# VM_Motor.net
KiCad netlist of a schematic drawn in EAGLE
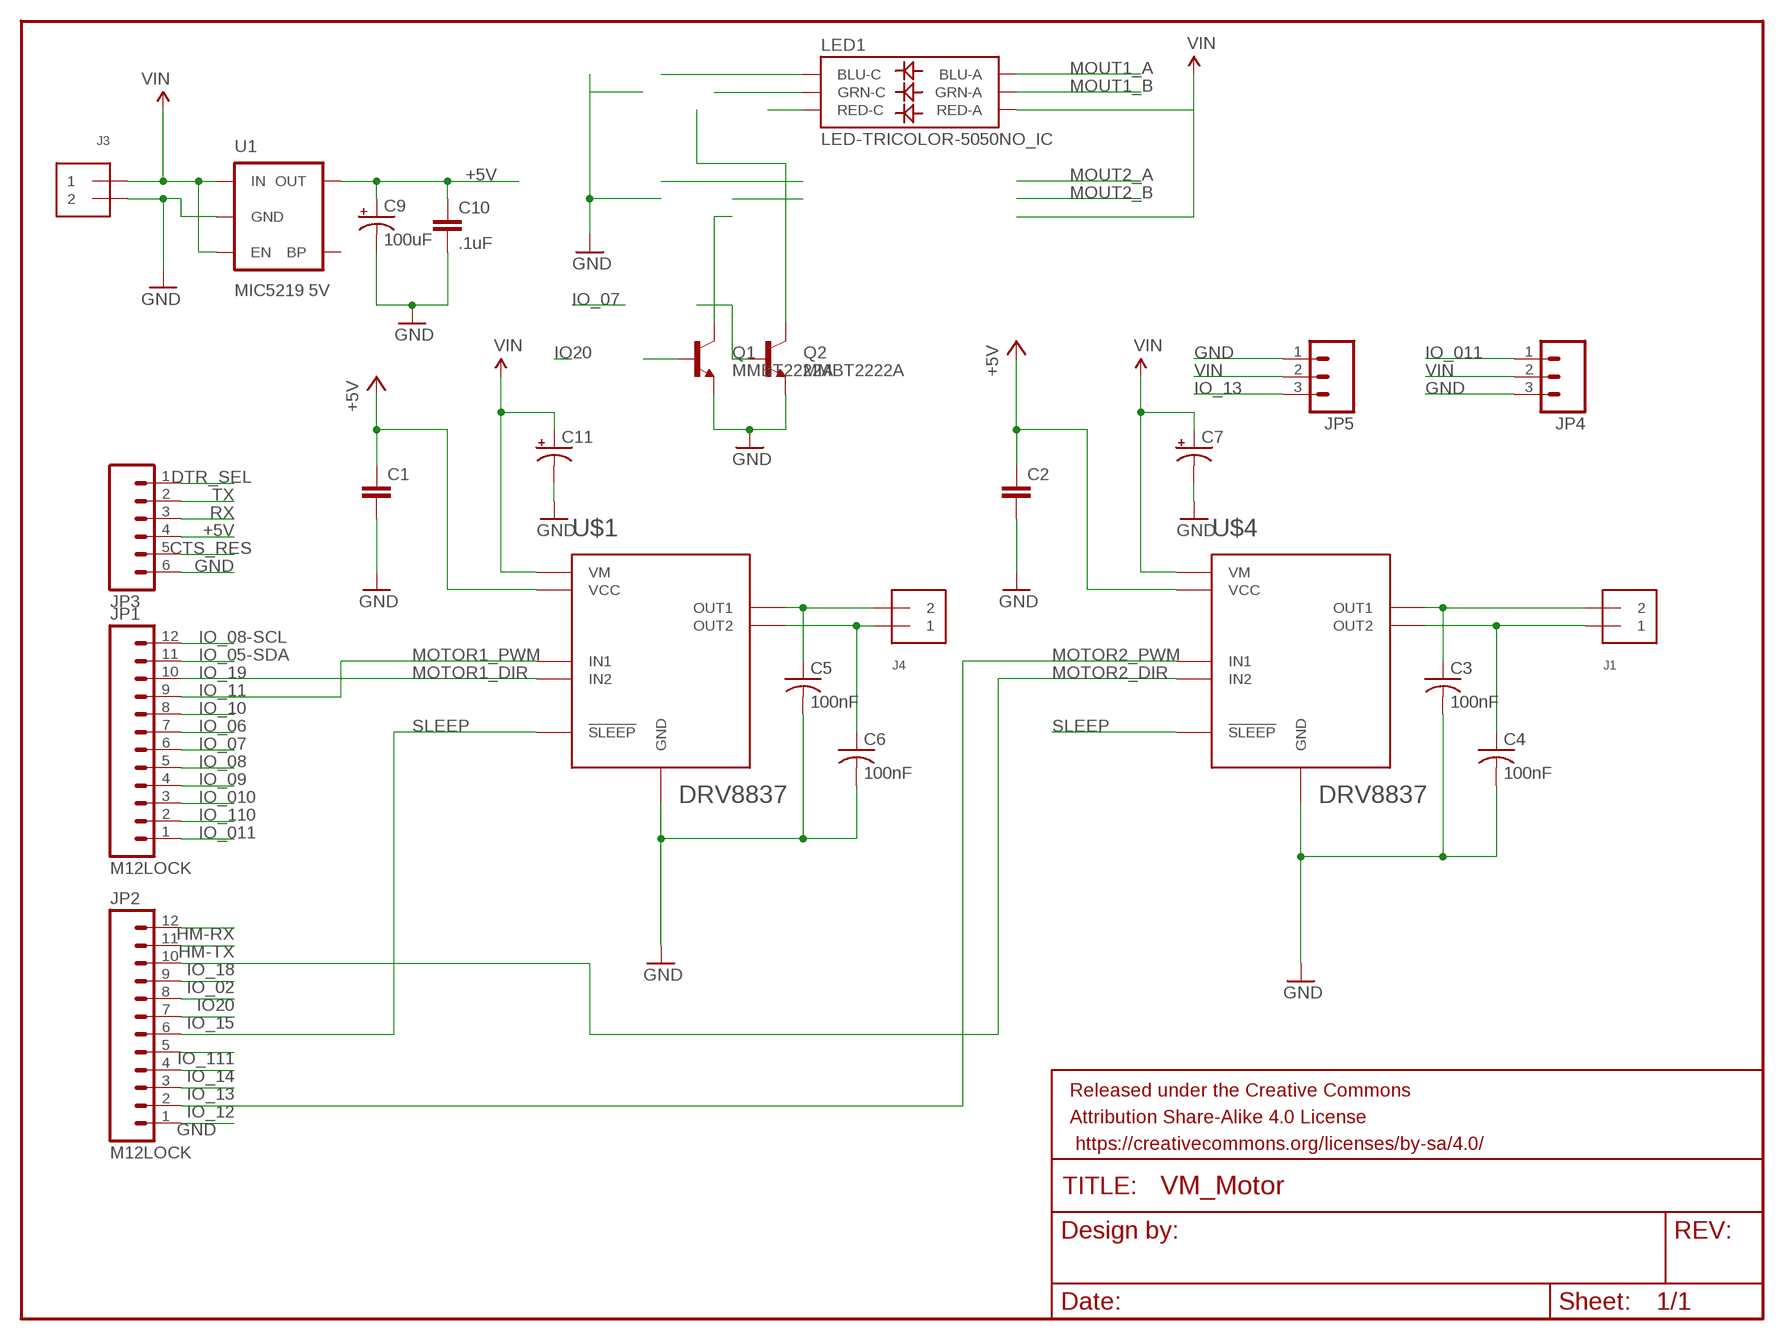
[diagram p0: schematic, sheet 1]

(export (version "E")
  (design (tool "Eeschema 10.0.6"))
  (components
    (comp (ref "C1")
      (value "CAP0402-CAP")
      (footprint "eagle-import:0402-CAP")
      (libsource (lib "eagle-import") (part "CAP0402-CAP"))
    )
    (comp (ref "C2")
      (value "CAP0402-CAP")
      (footprint "eagle-import:0402-CAP")
      (libsource (lib "eagle-import") (part "CAP0402-CAP"))
    )
    (comp (ref "C3")
      (value "100nF")
      (footprint "eagle-import:C0402")
      (libsource (lib "eagle-import") (part "C-USC0402"))
    )
    (comp (ref "C4")
      (value "100nF")
      (footprint "eagle-import:C0402")
      (libsource (lib "eagle-import") (part "C-USC0402"))
    )
    (comp (ref "C5")
      (value "100nF")
      (footprint "eagle-import:C0402")
      (libsource (lib "eagle-import") (part "C-USC0402"))
    )
    (comp (ref "C6")
      (value "100nF")
      (footprint "eagle-import:C0402")
      (libsource (lib "eagle-import") (part "C-USC0402"))
    )
    (comp (ref "C7")
      (value "CPOL-US140CLH-0810")
      (footprint "eagle-import:140CLH-0810")
      (libsource (lib "eagle-import") (part "CPOL-US140CLH-0810"))
    )
    (comp (ref "C9")
      (value "100uF")
      (footprint "eagle-import:EIA3528-KIT")
      (libsource (lib "eagle-import") (part "CAP_POL3528-KIT"))
    )
    (comp (ref "C10")
      (value ".1uF")
      (footprint "eagle-import:0402-CAP")
      (libsource (lib "eagle-import") (part "CAP0402-CAP"))
    )
    (comp (ref "C11")
      (value "CPOL-US140CLH-0810")
      (footprint "eagle-import:140CLH-0810")
      (libsource (lib "eagle-import") (part "CPOL-US140CLH-0810"))
    )
    (comp (ref "FRAME1")
      (value "FRAME-LETTER")
      (footprint "eagle-import:CREATIVE_COMMONS")
      (libsource (lib "eagle-import") (part "FRAME-LETTER"))
    )
    (comp (ref "J1")
      (value "TERMBLOCK_1X2")
      (footprint "eagle-import:TERMBLOCK_1X2-3.5MM")
      (libsource (lib "eagle-import") (part "TERMBLOCK_1X2"))
    )
    (comp (ref "J3")
      (value "TERMBLOCK_1X2")
      (footprint "eagle-import:TERMBLOCK_1X2-3.5MM")
      (libsource (lib "eagle-import") (part "TERMBLOCK_1X2"))
    )
    (comp (ref "J4")
      (value "TERMBLOCK_1X2")
      (footprint "eagle-import:TERMBLOCK_1X2-3.5MM")
      (libsource (lib "eagle-import") (part "TERMBLOCK_1X2"))
    )
    (comp (ref "JP1")
      (value "M12LOCK")
      (footprint "eagle-import:1X12_LOCK")
      (libsource (lib "eagle-import") (part "M12LOCK"))
    )
    (comp (ref "JP2")
      (value "M12LOCK")
      (footprint "eagle-import:1X12_LOCK")
      (libsource (lib "eagle-import") (part "M12LOCK"))
    )
    (comp (ref "JP3")
      (value "M06LOCK")
      (footprint "eagle-import:1X06_LOCK")
      (libsource (lib "eagle-import") (part "M06LOCK"))
    )
    (comp (ref "JP4")
      (value "M03LOCK")
      (footprint "eagle-import:1X03_LOCK")
      (libsource (lib "eagle-import") (part "M03LOCK"))
    )
    (comp (ref "JP5")
      (value "M03LOCK")
      (footprint "eagle-import:1X03_LOCK")
      (libsource (lib "eagle-import") (part "M03LOCK"))
    )
    (comp (ref "LED1")
      (value "LED-TRICOLOR-5050NO_IC")
      (footprint "eagle-import:LED-TRICOLOR-5050")
      (libsource (lib "eagle-import") (part "LED-TRICOLOR-5050NO_IC"))
    )
    (comp (ref "Q1")
      (value "MMBT2222A")
      (footprint "eagle-import:SOT23-3")
      (libsource (lib "eagle-import") (part "TRANSISTOR_NPNMMBT2222A"))
    )
    (comp (ref "Q2")
      (value "MMBT2222A")
      (footprint "eagle-import:SOT23-3")
      (libsource (lib "eagle-import") (part "TRANSISTOR_NPNMMBT2222A"))
    )
    (comp (ref "U$1")
      (value "DRV8837")
      (footprint "eagle-import:QFN8")
      (libsource (lib "eagle-import") (part "DRV8837"))
    )
    (comp (ref "U$4")
      (value "DRV8837")
      (footprint "eagle-import:QFN8")
      (libsource (lib "eagle-import") (part "DRV8837"))
    )
    (comp (ref "U1")
      (value "MIC5219 5V")
      (footprint "eagle-import:SOT23-5")
      (libsource (lib "eagle-import") (part "V_REG_MIC52195V"))
    )
  )
  (nets
    (net (code "1") (name "+5V") (class "Default")
      (node (ref "C1") (pin "1") (pinfunction "1_1") (pintype "passive"))
      (node (ref "C10") (pin "1") (pinfunction "1_1") (pintype "passive"))
      (node (ref "C2") (pin "1") (pinfunction "1_1") (pintype "passive"))
      (node (ref "C9") (pin "A") (pinfunction "+_A") (pintype "passive"))
      (node (ref "JP3") (pin "4") (pinfunction "4_4") (pintype "passive"))
      (node (ref "U$1") (pin "P$8") (pinfunction "VCC_P$8") (pintype "bidirectional"))
      (node (ref "U$4") (pin "P$8") (pinfunction "VCC_P$8") (pintype "bidirectional"))
      (node (ref "U1") (pin "5") (pinfunction "OUT_5") (pintype "passive"))
    )
    (net (code "2") (name "/CTS_RES") (class "Default")
      (node (ref "JP3") (pin "5") (pinfunction "5_5") (pintype "passive"))
    )
    (net (code "3") (name "/DTR_SEL") (class "Default")
      (node (ref "JP3") (pin "1") (pinfunction "1_1") (pintype "passive"))
    )
    (net (code "4") (name "/HM-RX") (class "Default")
      (node (ref "JP2") (pin "12") (pinfunction "12_12") (pintype "passive"))
    )
    (net (code "5") (name "/HM-TX") (class "Default")
      (node (ref "JP2") (pin "11") (pinfunction "11_11") (pintype "passive"))
    )
    (net (code "6") (name "/IO20") (class "Default")
      (node (ref "JP2") (pin "8") (pinfunction "8_8") (pintype "passive"))
    )
    (net (code "7") (name "/IO_02") (class "Default")
      (node (ref "JP2") (pin "9") (pinfunction "9_9") (pintype "passive"))
    )
    (net (code "8") (name "/IO_05-SDA") (class "Default")
      (node (ref "JP1") (pin "11") (pinfunction "11_11") (pintype "passive"))
    )
    (net (code "9") (name "/IO_06") (class "Default")
      (node (ref "JP1") (pin "7") (pinfunction "7_7") (pintype "passive"))
    )
    (net (code "10") (name "/IO_07") (class "Default")
      (node (ref "JP1") (pin "6") (pinfunction "6_6") (pintype "passive"))
    )
    (net (code "11") (name "/IO_08") (class "Default")
      (node (ref "JP1") (pin "5") (pinfunction "5_5") (pintype "passive"))
    )
    (net (code "12") (name "/IO_08-SCL") (class "Default")
      (node (ref "JP1") (pin "12") (pinfunction "12_12") (pintype "passive"))
    )
    (net (code "13") (name "/IO_09") (class "Default")
      (node (ref "JP1") (pin "4") (pinfunction "4_4") (pintype "passive"))
    )
    (net (code "14") (name "/IO_10") (class "Default")
      (node (ref "JP1") (pin "8") (pinfunction "8_8") (pintype "passive"))
    )
    (net (code "15") (name "/IO_010") (class "Default")
      (node (ref "JP1") (pin "3") (pinfunction "3_3") (pintype "passive"))
    )
    (net (code "16") (name "/IO_011") (class "Default")
      (node (ref "JP1") (pin "1") (pinfunction "1_1") (pintype "passive"))
      (node (ref "JP4") (pin "1") (pinfunction "1_1") (pintype "passive"))
    )
    (net (code "17") (name "/IO_13") (class "Default")
      (node (ref "JP2") (pin "3") (pinfunction "3_3") (pintype "passive"))
      (node (ref "JP5") (pin "3") (pinfunction "3_3") (pintype "passive"))
    )
    (net (code "18") (name "/IO_14") (class "Default")
      (node (ref "JP2") (pin "4") (pinfunction "4_4") (pintype "passive"))
    )
    (net (code "19") (name "/IO_15") (class "Default")
      (node (ref "JP2") (pin "7") (pinfunction "7_7") (pintype "passive"))
    )
    (net (code "20") (name "/IO_110") (class "Default")
      (node (ref "JP1") (pin "2") (pinfunction "2_2") (pintype "passive"))
    )
    (net (code "21") (name "/IO_111") (class "Default")
      (node (ref "JP2") (pin "5") (pinfunction "5_5") (pintype "passive"))
    )
    (net (code "22") (name "/MOTOR1_DIR") (class "Default")
      (node (ref "JP1") (pin "10") (pinfunction "10_10") (pintype "passive"))
      (node (ref "U$1") (pin "P$5") (pinfunction "IN2_P$5") (pintype "bidirectional"))
    )
    (net (code "23") (name "/MOTOR1_PWM") (class "Default")
      (node (ref "JP1") (pin "9") (pinfunction "9_9") (pintype "passive"))
      (node (ref "U$1") (pin "P$6") (pinfunction "IN1_P$6") (pintype "bidirectional"))
    )
    (net (code "24") (name "/MOTOR2_DIR") (class "Default")
      (node (ref "JP2") (pin "10") (pinfunction "10_10") (pintype "passive"))
      (node (ref "U$4") (pin "P$5") (pinfunction "IN2_P$5") (pintype "bidirectional"))
    )
    (net (code "25") (name "/MOTOR2_PWM") (class "Default")
      (node (ref "JP2") (pin "2") (pinfunction "2_2") (pintype "passive"))
      (node (ref "U$4") (pin "P$6") (pinfunction "IN1_P$6") (pintype "bidirectional"))
    )
    (net (code "26") (name "/MOUT1_A") (class "Default")
      (node (ref "C5") (pin "1") (pinfunction "1_1") (pintype "passive"))
      (node (ref "J4") (pin "2") (pinfunction "2_2") (pintype "passive"))
      (node (ref "LED1") (pin "3") (pinfunction "BLU-A_3") (pintype "bidirectional"))
      (node (ref "U$1") (pin "P$2") (pinfunction "OUT1_P$2") (pintype "bidirectional"))
    )
    (net (code "27") (name "/MOUT1_B") (class "Default")
      (node (ref "C6") (pin "1") (pinfunction "1_1") (pintype "passive"))
      (node (ref "J4") (pin "1") (pinfunction "1_1") (pintype "passive"))
      (node (ref "LED1") (pin "1") (pinfunction "GRN-A_1") (pintype "bidirectional"))
      (node (ref "U$1") (pin "P$3") (pinfunction "OUT2_P$3") (pintype "bidirectional"))
    )
    (net (code "28") (name "/MOUT2_A") (class "Default")
      (node (ref "C3") (pin "1") (pinfunction "1_1") (pintype "passive"))
      (node (ref "J1") (pin "2") (pinfunction "2_2") (pintype "passive"))
      (node (ref "U$4") (pin "P$2") (pinfunction "OUT1_P$2") (pintype "bidirectional"))
    )
    (net (code "29") (name "/MOUT2_B") (class "Default")
      (node (ref "C4") (pin "1") (pinfunction "1_1") (pintype "passive"))
      (node (ref "J1") (pin "1") (pinfunction "1_1") (pintype "passive"))
      (node (ref "U$4") (pin "P$3") (pinfunction "OUT2_P$3") (pintype "bidirectional"))
    )
    (net (code "30") (name "/RX") (class "Default")
      (node (ref "JP3") (pin "3") (pinfunction "3_3") (pintype "passive"))
    )
    (net (code "31") (name "/SLEEP") (class "Default")
      (node (ref "JP2") (pin "6") (pinfunction "6_6") (pintype "passive"))
      (node (ref "U$1") (pin "P$7") (pinfunction "~{SLEEP}_P$7") (pintype "bidirectional"))
      (node (ref "U$4") (pin "P$7") (pinfunction "~{SLEEP}_P$7") (pintype "bidirectional"))
    )
    (net (code "32") (name "/TX") (class "Default")
      (node (ref "JP3") (pin "2") (pinfunction "2_2") (pintype "passive"))
    )
    (net (code "33") (name "GND") (class "Default")
      (node (ref "C1") (pin "2") (pinfunction "2_2") (pintype "passive"))
      (node (ref "C10") (pin "2") (pinfunction "2_2") (pintype "passive"))
      (node (ref "C11") (pin "-") (pinfunction "-_-") (pintype "passive"))
      (node (ref "C2") (pin "2") (pinfunction "2_2") (pintype "passive"))
      (node (ref "C3") (pin "2") (pinfunction "2_2") (pintype "passive"))
      (node (ref "C4") (pin "2") (pinfunction "2_2") (pintype "passive"))
      (node (ref "C5") (pin "2") (pinfunction "2_2") (pintype "passive"))
      (node (ref "C6") (pin "2") (pinfunction "2_2") (pintype "passive"))
      (node (ref "C7") (pin "-") (pinfunction "-_-") (pintype "passive"))
      (node (ref "C9") (pin "C") (pinfunction "-_C") (pintype "passive"))
      (node (ref "J3") (pin "2") (pinfunction "2_2") (pintype "passive"))
      (node (ref "JP2") (pin "1") (pinfunction "1_1") (pintype "passive"))
      (node (ref "JP3") (pin "6") (pinfunction "6_6") (pintype "passive"))
      (node (ref "JP4") (pin "3") (pinfunction "3_3") (pintype "passive"))
      (node (ref "JP5") (pin "1") (pinfunction "1_1") (pintype "passive"))
      (node (ref "Q1") (pin "2") (pinfunction "E_2") (pintype "passive"))
      (node (ref "Q2") (pin "2") (pinfunction "E_2") (pintype "passive"))
      (node (ref "U$1") (pin "P$10") (pinfunction "GND_P$10") (pintype "bidirectional"))
      (node (ref "U$1") (pin "P$11") (pinfunction "GND_P$11") (pintype "bidirectional"))
      (node (ref "U$1") (pin "P$4") (pinfunction "GND_P$4") (pintype "bidirectional"))
      (node (ref "U$1") (pin "P$9") (pinfunction "GND_P$9") (pintype "bidirectional"))
      (node (ref "U$4") (pin "P$10") (pinfunction "GND_P$10") (pintype "bidirectional"))
      (node (ref "U$4") (pin "P$11") (pinfunction "GND_P$11") (pintype "bidirectional"))
      (node (ref "U$4") (pin "P$4") (pinfunction "GND_P$4") (pintype "bidirectional"))
      (node (ref "U$4") (pin "P$9") (pinfunction "GND_P$9") (pintype "bidirectional"))
      (node (ref "U1") (pin "2") (pinfunction "GND_2") (pintype "input"))
    )
    (net (code "34") (name "VIN") (class "Default")
      (node (ref "C11") (pin "+") (pinfunction "+_+") (pintype "passive"))
      (node (ref "C7") (pin "+") (pinfunction "+_+") (pintype "passive"))
      (node (ref "J3") (pin "1") (pinfunction "1_1") (pintype "passive"))
      (node (ref "JP4") (pin "2") (pinfunction "2_2") (pintype "passive"))
      (node (ref "JP5") (pin "2") (pinfunction "2_2") (pintype "passive"))
      (node (ref "LED1") (pin "2") (pinfunction "RED-A_2") (pintype "bidirectional"))
      (node (ref "U$1") (pin "P$1") (pinfunction "VM_P$1") (pintype "bidirectional"))
      (node (ref "U$4") (pin "P$1") (pinfunction "VM_P$1") (pintype "bidirectional"))
      (node (ref "U1") (pin "1") (pinfunction "IN_1") (pintype "input"))
      (node (ref "U1") (pin "3") (pinfunction "EN_3") (pintype "input"))
    )
    (net (code "35") (name "unconnected-(LED1-BLU-C-Pad4)") (class "Default")
      (node (ref "LED1") (pin "4") (pinfunction "BLU-C_4") (pintype "bidirectional"))
    )
    (net (code "36") (name "unconnected-(LED1-GRN-C-Pad6)") (class "Default")
      (node (ref "LED1") (pin "6") (pinfunction "GRN-C_6") (pintype "bidirectional"))
    )
    (net (code "37") (name "unconnected-(LED1-RED-C-Pad5)") (class "Default")
      (node (ref "LED1") (pin "5") (pinfunction "RED-C_5") (pintype "bidirectional"))
    )
    (net (code "38") (name "unconnected-(Q1-B-Pad1)") (class "Default")
      (node (ref "Q1") (pin "1") (pinfunction "B_1") (pintype "passive"))
    )
    (net (code "39") (name "unconnected-(Q1-C-Pad3)") (class "Default")
      (node (ref "Q1") (pin "3") (pinfunction "C_3") (pintype "passive"))
    )
    (net (code "40") (name "unconnected-(Q2-B-Pad1)") (class "Default")
      (node (ref "Q2") (pin "1") (pinfunction "B_1") (pintype "passive"))
    )
    (net (code "41") (name "unconnected-(Q2-C-Pad3)") (class "Default")
      (node (ref "Q2") (pin "3") (pinfunction "C_3") (pintype "passive"))
    )
    (net (code "42") (name "unconnected-(U1-BP-Pad4)") (class "Default")
      (node (ref "U1") (pin "4") (pinfunction "BP_4") (pintype "input"))
    )
  )
)
